# main.net
KiCad netlist of a schematic drawn in EAGLE
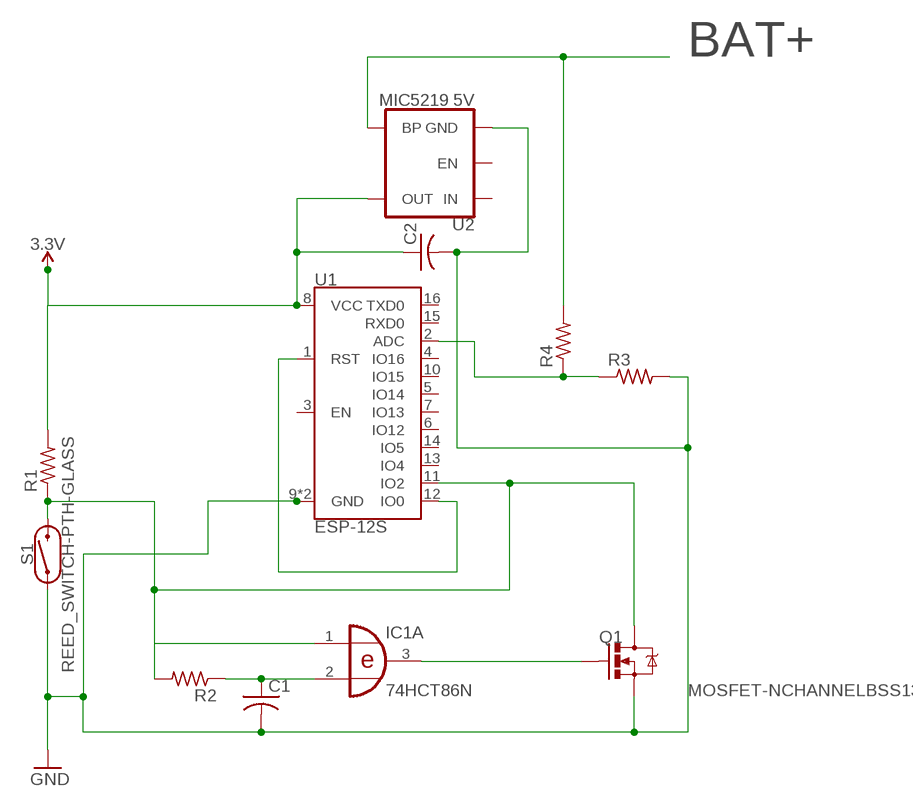
[diagram p0: schematic, sheet 1]

(export (version "E")
  (design (tool "Eeschema 10.0.6"))
  (components
    (comp (ref "C1")
      (value "C-US025-050X050")
      (footprint "eagle-import:C025-050X050")
      (libsource (lib "eagle-import") (part "C-US025-050X050"))
    )
    (comp (ref "C2")
      (value "C-US025-050X050")
      (footprint "eagle-import:C025-050X050")
      (libsource (lib "eagle-import") (part "C-US025-050X050"))
    )
    (comp (ref "IC1")
      (value "74HCT86N")
      (footprint "eagle-import:DIL14")
      (libsource (lib "eagle-import") (part "7486NHCT"))
    )
    (comp (ref "Q1")
      (value "MOSFET-NCHANNELBSS138")
      (footprint "eagle-import:SOT23")
      (libsource (lib "eagle-import") (part "MOSFET-NCHANNELBSS138"))
    )
    (comp (ref "R1")
      (value "R-US_0411/15")
      (footprint "eagle-import:0411_15")
      (libsource (lib "eagle-import") (part "R-US_0411/15"))
    )
    (comp (ref "R2")
      (value "R-US_0411/15")
      (footprint "eagle-import:0411_15")
      (libsource (lib "eagle-import") (part "R-US_0411/15"))
    )
    (comp (ref "R3")
      (value "R-US_0411/15")
      (footprint "eagle-import:0411_15")
      (libsource (lib "eagle-import") (part "R-US_0411/15"))
    )
    (comp (ref "R4")
      (value "R-US_0411/15")
      (footprint "eagle-import:0411_15")
      (libsource (lib "eagle-import") (part "R-US_0411/15"))
    )
    (comp (ref "S1")
      (value "REED_SWITCH-PTH-GLASS")
      (footprint "eagle-import:REED_SWITCH_GLASS")
      (libsource (lib "eagle-import") (part "REED_SWITCH-PTH-GLASS"))
    )
    (comp (ref "U1")
      (value "ESP-12S")
      (footprint "eagle-import:ESP-12S")
      (libsource (lib "eagle-import") (part "ESP-12S"))
    )
    (comp (ref "U2")
      (value "MIC5219 5V")
      (footprint "eagle-import:SOT23-5")
      (libsource (lib "eagle-import") (part "V_REG_MIC52195V"))
    )
  )
  (nets
    (net (code "1") (name "/BAT+") (class "Default")
      (node (ref "R4") (pin "2") (pinfunction "2_2") (pintype "passive"))
      (node (ref "U2") (pin "4") (pinfunction "BP_4") (pintype "input"))
    )
    (net (code "2") (name "3.3V") (class "Default")
      (node (ref "C2") (pin "1") (pinfunction "1_1") (pintype "passive"))
      (node (ref "R1") (pin "2") (pinfunction "2_2") (pintype "passive"))
      (node (ref "U1") (pin "8") (pinfunction "VCC_8") (pintype "bidirectional"))
      (node (ref "U2") (pin "5") (pinfunction "OUT_5") (pintype "passive"))
    )
    (net (code "3") (name "GND") (class "Default")
      (node (ref "C1") (pin "2") (pinfunction "2_2") (pintype "passive"))
      (node (ref "C2") (pin "2") (pinfunction "2_2") (pintype "passive"))
      (node (ref "Q1") (pin "2") (pinfunction "S_2") (pintype "passive"))
      (node (ref "R3") (pin "2") (pinfunction "2_2") (pintype "passive"))
      (node (ref "S1") (pin "P$1") (pinfunction "1_P$1") (pintype "passive"))
      (node (ref "U1") (pin "9") (pinfunction "GND_9") (pintype "bidirectional"))
      (node (ref "U1") (pin "P$1") (pinfunction "GND_P$1") (pintype "bidirectional"))
      (node (ref "U2") (pin "2") (pinfunction "GND_2") (pintype "input"))
    )
    (net (code "4") (name "Net-(IC1A-I0)") (class "Default")
      (node (ref "IC1") (pin "1") (pinfunction "I0_1") (pintype "input"))
      (node (ref "Q1") (pin "3") (pinfunction "D_3") (pintype "passive"))
      (node (ref "R1") (pin "1") (pinfunction "1_1") (pintype "passive"))
      (node (ref "R2") (pin "2") (pinfunction "2_2") (pintype "passive"))
      (node (ref "S1") (pin "P$2") (pinfunction "2_P$2") (pintype "passive"))
      (node (ref "U1") (pin "11") (pinfunction "IO2_11") (pintype "bidirectional"))
    )
    (net (code "5") (name "Net-(IC1A-I1)") (class "Default")
      (node (ref "C1") (pin "1") (pinfunction "1_1") (pintype "passive"))
      (node (ref "IC1") (pin "2") (pinfunction "I1_2") (pintype "input"))
      (node (ref "R2") (pin "1") (pinfunction "1_1") (pintype "passive"))
    )
    (net (code "6") (name "Net-(IC1A-O)") (class "Default")
      (node (ref "IC1") (pin "3") (pinfunction "O_3") (pintype "output"))
      (node (ref "Q1") (pin "1") (pinfunction "G_1") (pintype "passive"))
    )
    (net (code "7") (name "Net-(U1-ADC)") (class "Default")
      (node (ref "R3") (pin "1") (pinfunction "1_1") (pintype "passive"))
      (node (ref "R4") (pin "1") (pinfunction "1_1") (pintype "passive"))
      (node (ref "U1") (pin "2") (pinfunction "ADC_2") (pintype "bidirectional"))
    )
    (net (code "8") (name "Net-(U1-IO0)") (class "Default")
      (node (ref "U1") (pin "1") (pinfunction "RST_1") (pintype "bidirectional"))
      (node (ref "U1") (pin "12") (pinfunction "IO0_12") (pintype "bidirectional"))
    )
    (net (code "9") (name "unconnected-(U1-EN-Pad3)") (class "Default")
      (node (ref "U1") (pin "3") (pinfunction "EN_3") (pintype "bidirectional"))
    )
    (net (code "10") (name "unconnected-(U1-IO4-Pad13)") (class "Default")
      (node (ref "U1") (pin "13") (pinfunction "IO4_13") (pintype "bidirectional"))
    )
    (net (code "11") (name "unconnected-(U1-IO5-Pad14)") (class "Default")
      (node (ref "U1") (pin "14") (pinfunction "IO5_14") (pintype "bidirectional"))
    )
    (net (code "12") (name "unconnected-(U1-IO12-Pad6)") (class "Default")
      (node (ref "U1") (pin "6") (pinfunction "IO12_6") (pintype "bidirectional"))
    )
    (net (code "13") (name "unconnected-(U1-IO13-Pad7)") (class "Default")
      (node (ref "U1") (pin "7") (pinfunction "IO13_7") (pintype "bidirectional"))
    )
    (net (code "14") (name "unconnected-(U1-IO14-Pad5)") (class "Default")
      (node (ref "U1") (pin "5") (pinfunction "IO14_5") (pintype "bidirectional"))
    )
    (net (code "15") (name "unconnected-(U1-IO15-Pad10)") (class "Default")
      (node (ref "U1") (pin "10") (pinfunction "IO15_10") (pintype "bidirectional"))
    )
    (net (code "16") (name "unconnected-(U1-IO16-Pad4)") (class "Default")
      (node (ref "U1") (pin "4") (pinfunction "IO16_4") (pintype "bidirectional"))
    )
    (net (code "17") (name "unconnected-(U1-RXD0-Pad15)") (class "Default")
      (node (ref "U1") (pin "15") (pinfunction "RXD0_15") (pintype "bidirectional"))
    )
    (net (code "18") (name "unconnected-(U1-TXD0-Pad16)") (class "Default")
      (node (ref "U1") (pin "16") (pinfunction "TXD0_16") (pintype "bidirectional"))
    )
    (net (code "19") (name "unconnected-(U2-EN-Pad3)") (class "Default")
      (node (ref "U2") (pin "3") (pinfunction "EN_3") (pintype "input"))
    )
    (net (code "20") (name "unconnected-(U2-IN-Pad1)") (class "Default")
      (node (ref "U2") (pin "1") (pinfunction "IN_1") (pintype "input"))
    )
  )
)
